# Feedback.net
KiCad netlist of a schematic drawn in Altium Designer
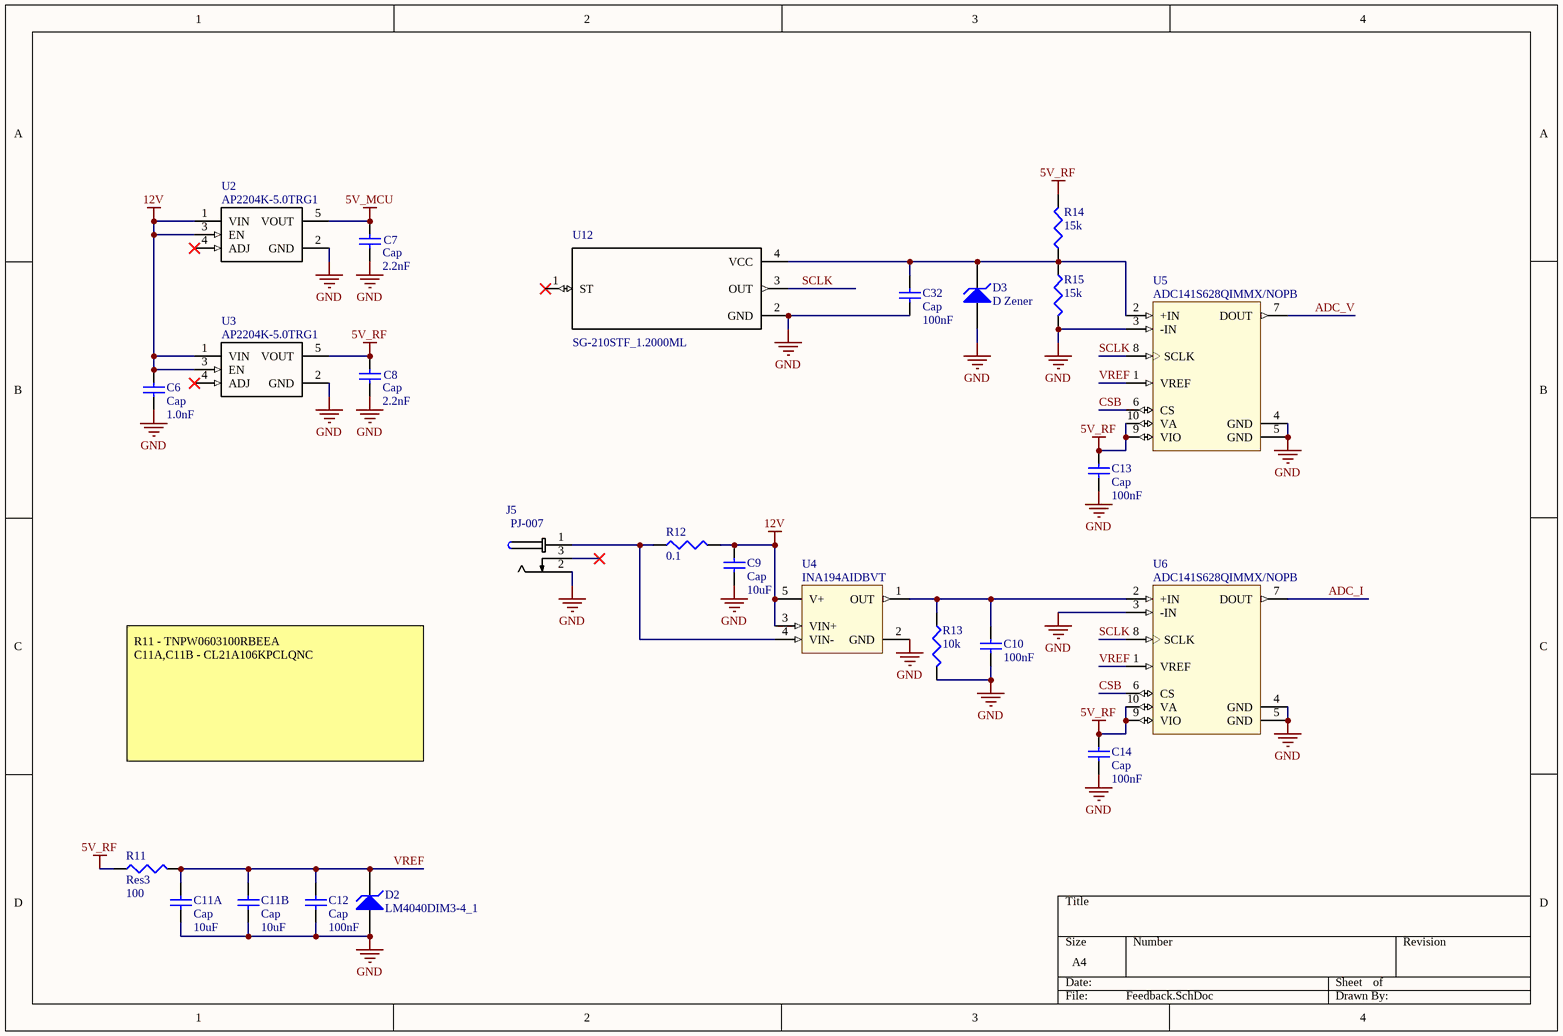
[diagram p0: Feedback.SchDoc]

(export (version "E")
  (design (tool "Eeschema 10.0.6"))
  (components
    (comp (ref "C6")
      (value "Cap")
      (footprint "1608[0603]")
      (description "Capacitor (Semiconductor SIM Model)")
      (fields (field (name "ALTIUM_VALUE") "1.0nF") (field (name "PUBLISHER") "Altium Limited"))
      (libsource (lib "Miscellaneous Devices") (part "Cap Semi"))
    )
    (comp (ref "C7")
      (value "Cap")
      (footprint "1608[0603]")
      (description "Capacitor (Semiconductor SIM Model)")
      (fields (field (name "ALTIUM_VALUE") "2.2nF") (field (name "PUBLISHER") "Altium Limited"))
      (libsource (lib "Miscellaneous Devices") (part "Cap Semi"))
    )
    (comp (ref "C8")
      (value "Cap")
      (footprint "1608[0603]")
      (description "Capacitor (Semiconductor SIM Model)")
      (fields (field (name "ALTIUM_VALUE") "2.2nF") (field (name "PUBLISHER") "Altium Limited"))
      (libsource (lib "Miscellaneous Devices") (part "Cap Semi"))
    )
    (comp (ref "C9")
      (value "Cap")
      (footprint "C0805")
      (description "Capacitor (Semiconductor SIM Model)")
      (fields (field (name "ALTIUM_VALUE") "10uF") (field (name "PUBLISHER") "Altium Limited"))
      (libsource (lib "Miscellaneous Devices") (part "Cap Semi"))
    )
    (comp (ref "C10")
      (value "100nF")
      (footprint "1608[0603]")
      (description "Capacitor (Semiconductor SIM Model)")
      (fields (field (name "PUBLISHER") "Altium Limited"))
      (libsource (lib "Miscellaneous Devices") (part "Cap Semi"))
    )
    (comp (ref "C11A")
      (value "Cap")
      (footprint "C0805")
      (description "Capacitor (Semiconductor SIM Model)")
      (fields (field (name "ALTIUM_VALUE") "10uF") (field (name "PUBLISHER") "Altium Limited"))
      (libsource (lib "Miscellaneous Devices") (part "Cap Semi"))
    )
    (comp (ref "C11B")
      (value "Cap")
      (footprint "C0805")
      (description "Capacitor (Semiconductor SIM Model)")
      (fields (field (name "ALTIUM_VALUE") "10uF") (field (name "PUBLISHER") "Altium Limited"))
      (libsource (lib "Miscellaneous Devices") (part "Cap Semi"))
    )
    (comp (ref "C12")
      (value "Cap")
      (footprint "1608[0603]")
      (description "Capacitor (Semiconductor SIM Model)")
      (fields (field (name "ALTIUM_VALUE") "100nF") (field (name "PUBLISHER") "Altium Limited"))
      (libsource (lib "Miscellaneous Devices") (part "Cap Semi"))
    )
    (comp (ref "C13")
      (value "Cap")
      (footprint "1608[0603]")
      (description "Capacitor (Semiconductor SIM Model)")
      (fields (field (name "ALTIUM_VALUE") "100nF") (field (name "PUBLISHER") "Altium Limited"))
      (libsource (lib "Miscellaneous Devices") (part "Cap Semi"))
    )
    (comp (ref "C14")
      (value "Cap")
      (footprint "1608[0603]")
      (description "Capacitor (Semiconductor SIM Model)")
      (fields (field (name "ALTIUM_VALUE") "100nF") (field (name "PUBLISHER") "Altium Limited"))
      (libsource (lib "Miscellaneous Devices") (part "Cap Semi"))
    )
    (comp (ref "C32")
      (value "Cap")
      (footprint "1608[0603]")
      (description "Capacitor (Semiconductor SIM Model)")
      (fields (field (name "ALTIUM_VALUE") "100nF") (field (name "PUBLISHER") "Altium Limited"))
      (libsource (lib "Miscellaneous Devices") (part "Cap Semi"))
    )
    (comp (ref "D2")
      (value "LM4040DIM3-4_1")
      (footprint "SOT95P237X112-3N")
      (description "IC VREF SHUNT 4.096V SOT23")
      (fields (field (name "MF") "Texas Instruments") (field (name "MP") "LM404DIM4-4.1"))
      (libsource (lib "Vocore2Parts") (part "LM4040DIM3-4_1"))
    )
    (comp (ref "D3")
      (value "D Zener")
      (footprint "SODFL250X110-2N")
      (description "Zener Diode")
      (fields (field (name "PUBLISHER") "Altium Limited"))
      (libsource (lib "Miscellaneous Devices") (part "D Zener"))
    )
    (comp (ref "J5")
      (value "PJ-007")
      (footprint "PJ-007")
      (description "1.3 mm Center Pin, 1.0 A, Right Angle, Through Hole, Dc Power Jack Connector")
      (fields (field (name "MF") "CUI"))
      (libsource (lib "Vocore2Parts") (part "PJ-007"))
    )
    (comp (ref "R11")
      (value "Res3")
      (footprint "J1-0603")
      (description "Resistor")
      (fields (field (name "ALTIUM_VALUE") "100") (field (name "PUBLISHER") "Altium Limited"))
      (libsource (lib "Miscellaneous Devices") (part "Res3"))
    )
    (comp (ref "R12")
      (value "0.1")
      (footprint "TO-252-3")
      (description "Resistor")
      (fields (field (name "PUBLISHER") "Altium Limited"))
      (libsource (lib "Miscellaneous Devices") (part "Res3"))
    )
    (comp (ref "R13")
      (value "10k")
      (footprint "J1-0603")
      (description "Resistor")
      (fields (field (name "PUBLISHER") "Altium Limited"))
      (libsource (lib "Miscellaneous Devices") (part "Res3"))
    )
    (comp (ref "R14")
      (value "15k")
      (footprint "J1-0603")
      (description "Resistor")
      (fields (field (name "PUBLISHER") "Altium Limited"))
      (libsource (lib "Miscellaneous Devices") (part "Res3"))
    )
    (comp (ref "R15")
      (value "15k")
      (footprint "J1-0603")
      (description "Resistor")
      (fields (field (name "PUBLISHER") "Altium Limited"))
      (libsource (lib "Miscellaneous Devices") (part "Res3"))
    )
    (comp (ref "U2")
      (value "AP2204K-5.0TRG1")
      (footprint "SOT95P280X145-5N")
      (description "IC REG LINEAR 5V 150MA SOT23-5")
      (fields (field (name "MF") "Diodes Inc."))
      (libsource (lib "Vocore2Parts") (part "AP2204K-5.0TRG1"))
    )
    (comp (ref "U3")
      (value "AP2204K-5.0TRG1")
      (footprint "SOT95P280X145-5N")
      (description "IC REG LINEAR 5V 150MA SOT23-5")
      (fields (field (name "MF") "Diodes Inc."))
      (libsource (lib "Vocore2Parts") (part "AP2204K-5.0TRG1"))
    )
    (comp (ref "U4")
      (value "INA194AIDBVT")
      (footprint "SOT95P280X145-5N")
      (description "IC CURRENT MONITOR 3% SOT23-5")
      (fields (field (name "MF") "Texas Instruments"))
      (libsource (lib "Vocore2Parts") (part "INA194AIDBVT"))
    )
    (comp (ref "U5")
      (value "ADC141S628QIMMX/NOPB")
      (footprint "SOP50P490X110-11N")
      (description "IC CONVERTER A/D 14-BIT 10-MSOP")
      (fields (field (name "MF") "Texas Instruments"))
      (libsource (lib "Vocore2Parts") (part "ADC141S628QIMMX/NOPB"))
    )
    (comp (ref "U6")
      (value "ADC141S628QIMMX/NOPB")
      (footprint "SOP50P490X110-11N")
      (description "IC CONVERTER A/D 14-BIT 10-MSOP")
      (fields (field (name "MF") "Texas Instruments"))
      (libsource (lib "Vocore2Parts") (part "ADC141S628QIMMX/NOPB"))
    )
    (comp (ref "U12")
      (value "SG-210STF_1.2000ML")
      (footprint "OSCCC200X160X50")
      (description "Spxo 1.6-3.6v 50ppm -40/+85c")
      (fields (field (name "MP") "SG-210STF 1.2000ML") (field (name "MF") "EPSON"))
      (libsource (lib "Vocore2Parts") (part "SG-210STF_1.2000ML"))
    )
  )
  (nets
    (net (code "1") (name "/ADC_I") (class "Default")
      (node (ref "U6") (pin "7") (pinfunction "DOUT_7") (pintype "output"))
    )
    (net (code "2") (name "/ADC_V") (class "Default")
      (node (ref "U5") (pin "7") (pinfunction "DOUT_7") (pintype "output"))
    )
    (net (code "3") (name "/CSB") (class "Default")
      (node (ref "U5") (pin "6") (pinfunction "CS_6") (pintype "bidirectional"))
      (node (ref "U6") (pin "6") (pinfunction "CS_6") (pintype "bidirectional"))
    )
    (net (code "4") (name "/SCLK") (class "Default")
      (node (ref "U12") (pin "3") (pinfunction "OUT_3") (pintype "output"))
      (node (ref "U5") (pin "8") (pinfunction "SCLK_8") (pintype "input"))
      (node (ref "U6") (pin "8") (pinfunction "SCLK_8") (pintype "input"))
    )
    (net (code "5") (name "/VREF") (class "Default")
      (node (ref "C11A") (pin "1") (pinfunction "1_1") (pintype "passive"))
      (node (ref "C11B") (pin "1") (pinfunction "1_1") (pintype "passive"))
      (node (ref "C12") (pin "1") (pinfunction "1_1") (pintype "passive"))
      (node (ref "D2") (pin "2") (pinfunction "K_2") (pintype "passive"))
      (node (ref "R11") (pin "1") (pinfunction "1_1") (pintype "passive"))
      (node (ref "U5") (pin "1") (pinfunction "VREF_1") (pintype "input"))
      (node (ref "U6") (pin "1") (pinfunction "VREF_1") (pintype "input"))
    )
    (net (code "6") (name "5V_MCU") (class "Default")
      (node (ref "C7") (pin "2") (pinfunction "2_2") (pintype "passive"))
      (node (ref "U2") (pin "5") (pinfunction "VOUT_5") (pintype "power_in"))
    )
    (net (code "7") (name "5V_RF") (class "Default")
      (node (ref "C13") (pin "1") (pinfunction "1_1") (pintype "passive"))
      (node (ref "C14") (pin "1") (pinfunction "1_1") (pintype "passive"))
      (node (ref "C8") (pin "2") (pinfunction "2_2") (pintype "passive"))
      (node (ref "R11") (pin "2") (pinfunction "2_2") (pintype "passive"))
      (node (ref "R14") (pin "1") (pinfunction "1_1") (pintype "passive"))
      (node (ref "U3") (pin "5") (pinfunction "VOUT_5") (pintype "power_in"))
      (node (ref "U5") (pin "10") (pinfunction "VA_10") (pintype "bidirectional"))
      (node (ref "U5") (pin "9") (pinfunction "VIO_9") (pintype "bidirectional"))
      (node (ref "U6") (pin "10") (pinfunction "VA_10") (pintype "bidirectional"))
      (node (ref "U6") (pin "9") (pinfunction "VIO_9") (pintype "bidirectional"))
    )
    (net (code "8") (name "12V") (class "Default")
      (node (ref "C6") (pin "1") (pinfunction "1_1") (pintype "passive"))
      (node (ref "C9") (pin "1") (pinfunction "1_1") (pintype "passive"))
      (node (ref "R12") (pin "1") (pinfunction "1_1") (pintype "passive"))
      (node (ref "U2") (pin "1") (pinfunction "VIN_1") (pintype "power_in"))
      (node (ref "U2") (pin "3") (pinfunction "EN_3") (pintype "input"))
      (node (ref "U3") (pin "1") (pinfunction "VIN_1") (pintype "power_in"))
      (node (ref "U3") (pin "3") (pinfunction "EN_3") (pintype "input"))
      (node (ref "U4") (pin "3") (pinfunction "VIN+_3") (pintype "input"))
      (node (ref "U4") (pin "5") (pinfunction "V+_5") (pintype "power_in"))
    )
    (net (code "9") (name "GND") (class "Default")
      (node (ref "C10") (pin "1") (pinfunction "1_1") (pintype "passive"))
      (node (ref "C11A") (pin "2") (pinfunction "2_2") (pintype "passive"))
      (node (ref "C11B") (pin "2") (pinfunction "2_2") (pintype "passive"))
      (node (ref "C12") (pin "2") (pinfunction "2_2") (pintype "passive"))
      (node (ref "C13") (pin "2") (pinfunction "2_2") (pintype "passive"))
      (node (ref "C14") (pin "2") (pinfunction "2_2") (pintype "passive"))
      (node (ref "C32") (pin "2") (pinfunction "2_2") (pintype "passive"))
      (node (ref "C6") (pin "2") (pinfunction "2_2") (pintype "passive"))
      (node (ref "C7") (pin "1") (pinfunction "1_1") (pintype "passive"))
      (node (ref "C8") (pin "1") (pinfunction "1_1") (pintype "passive"))
      (node (ref "C9") (pin "2") (pinfunction "2_2") (pintype "passive"))
      (node (ref "D2") (pin "1") (pinfunction "A_1") (pintype "passive"))
      (node (ref "D3") (pin "1") (pinfunction "A_1") (pintype "passive"))
      (node (ref "J5") (pin "2") (pinfunction "S_2") (pintype "passive"))
      (node (ref "R13") (pin "2") (pinfunction "2_2") (pintype "passive"))
      (node (ref "R15") (pin "1") (pinfunction "1_1") (pintype "passive"))
      (node (ref "U12") (pin "2") (pinfunction "GND_2") (pintype "power_in"))
      (node (ref "U2") (pin "2") (pinfunction "GND_2") (pintype "power_in"))
      (node (ref "U3") (pin "2") (pinfunction "GND_2") (pintype "power_in"))
      (node (ref "U4") (pin "2") (pinfunction "GND_2") (pintype "passive"))
      (node (ref "U5") (pin "3") (pinfunction "-IN_3") (pintype "input"))
      (node (ref "U5") (pin "4") (pinfunction "GND_4") (pintype "power_in"))
      (node (ref "U5") (pin "5") (pinfunction "GND_5") (pintype "power_in"))
      (node (ref "U6") (pin "3") (pinfunction "-IN_3") (pintype "input"))
      (node (ref "U6") (pin "4") (pinfunction "GND_4") (pintype "power_in"))
      (node (ref "U6") (pin "5") (pinfunction "GND_5") (pintype "power_in"))
    )
    (net (code "10") (name "Net-(D3-K)") (class "Default")
      (node (ref "C32") (pin "1") (pinfunction "1_1") (pintype "passive"))
      (node (ref "D3") (pin "2") (pinfunction "K_2") (pintype "passive"))
      (node (ref "R14") (pin "2") (pinfunction "2_2") (pintype "passive"))
      (node (ref "R15") (pin "2") (pinfunction "2_2") (pintype "passive"))
      (node (ref "U12") (pin "4") (pinfunction "VCC_4") (pintype "power_in"))
      (node (ref "U5") (pin "2") (pinfunction "+IN_2") (pintype "input"))
    )
    (net (code "11") (name "Net-(J5-T)") (class "Default")
      (node (ref "J5") (pin "1") (pinfunction "T_1") (pintype "passive"))
      (node (ref "R12") (pin "2") (pinfunction "2_2") (pintype "passive"))
      (node (ref "U4") (pin "4") (pinfunction "VIN-_4") (pintype "input"))
    )
    (net (code "12") (name "Net-(U4-OUT)") (class "Default")
      (node (ref "C10") (pin "2") (pinfunction "2_2") (pintype "passive"))
      (node (ref "R13") (pin "1") (pinfunction "1_1") (pintype "passive"))
      (node (ref "U4") (pin "1") (pinfunction "OUT_1") (pintype "output"))
      (node (ref "U6") (pin "2") (pinfunction "+IN_2") (pintype "input"))
    )
    (net (code "13") (name "unconnected-(J5-SS-Pad3)") (class "Default")
      (node (ref "J5") (pin "3") (pinfunction "SS_3") (pintype "passive+no_connect"))
    )
    (net (code "14") (name "unconnected-(U2-ADJ-Pad4)") (class "Default")
      (node (ref "U2") (pin "4") (pinfunction "ADJ_4") (pintype "input+no_connect"))
    )
    (net (code "15") (name "unconnected-(U3-ADJ-Pad4)") (class "Default")
      (node (ref "U3") (pin "4") (pinfunction "ADJ_4") (pintype "input+no_connect"))
    )
    (net (code "16") (name "unconnected-(U12-ST-Pad1)") (class "Default")
      (node (ref "U12") (pin "1") (pinfunction "ST_1") (pintype "bidirectional+no_connect"))
    )
  )
)
